# Microcontroller.net
KiCad netlist of a schematic drawn in Altium Designer
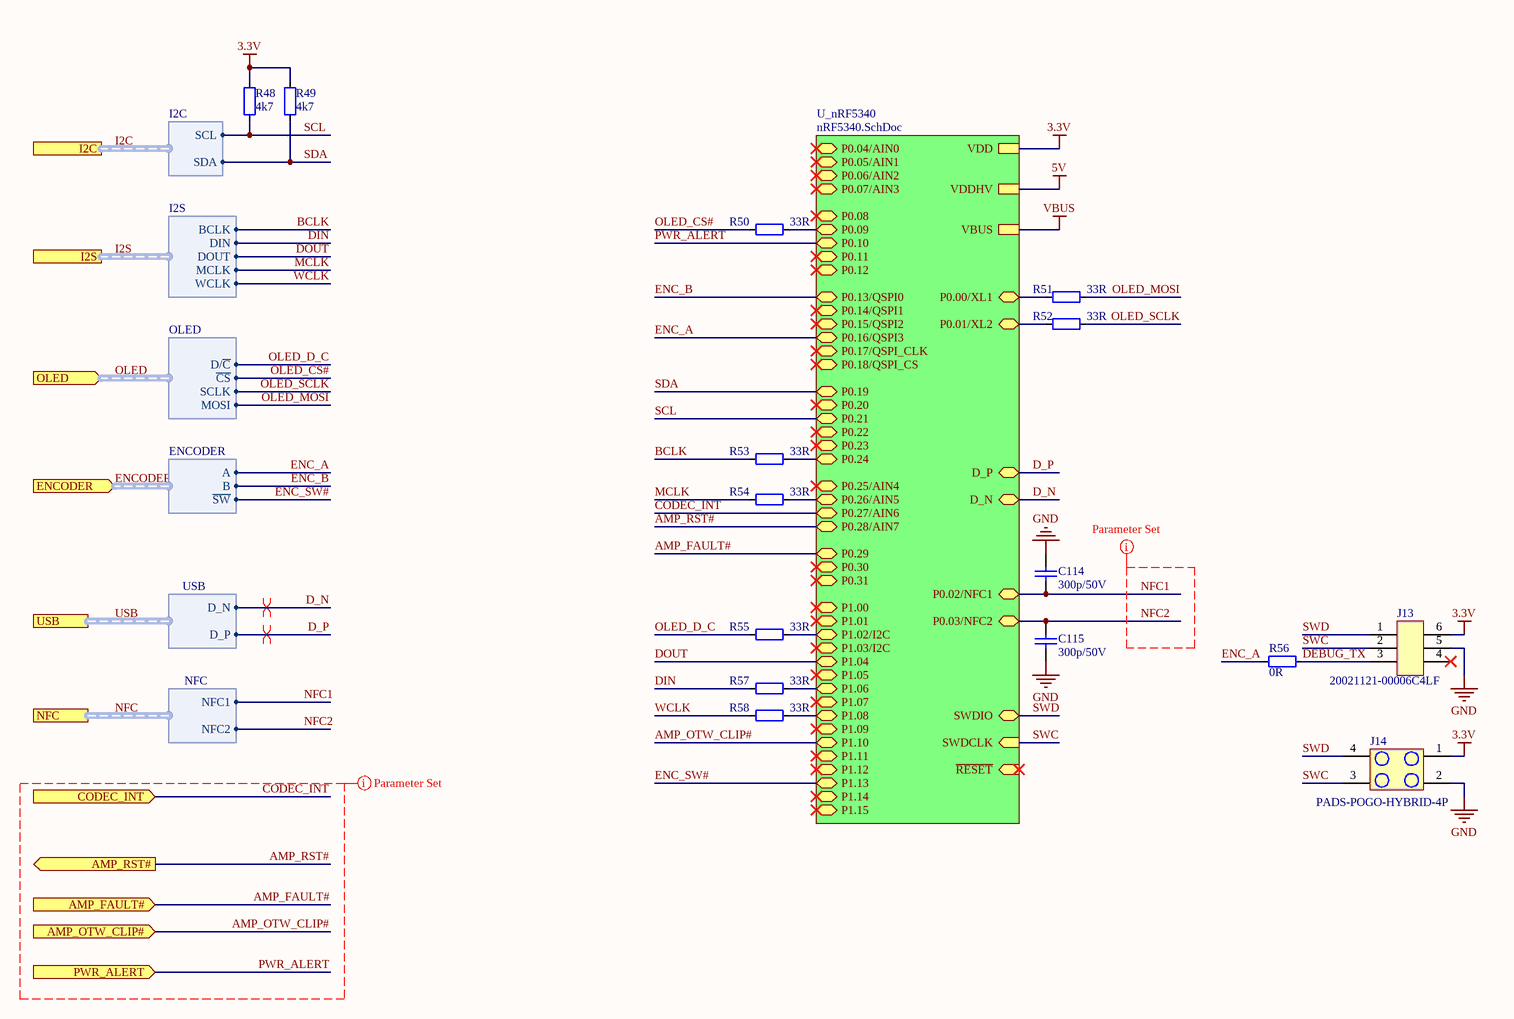
[diagram p0: Microcontroller.SchDoc]

(export (version "E")
  (design (tool "Eeschema 10.0.6"))
  (components
    (comp (ref "C114")
      (value "300p/50V")
      (footprint "C0402")
      (fields (field (name "VOLTAGE") "50V") (field (name "TOLERANCE") "10%"))
      (libsource (lib "dk_capacitors") (part "300p 50V X7R 0402"))
    )
    (comp (ref "C115")
      (value "300p/50V")
      (footprint "C0402")
      (fields (field (name "VOLTAGE") "50V") (field (name "TOLERANCE") "10%"))
      (libsource (lib "dk_capacitors") (part "300p 50V X7R 0402"))
    )
    (comp (ref "J13")
      (value "20021121-00006C4LF")
      (footprint "20021121-00006C4LF")
      (description "Connector Header Surface Mount 6 position 0.050\" (1.27mm)")
      (libsource (lib "dk_connectors") (part "20021121-00006C4LF"))
    )
    (comp (ref "J14")
      (value "PADS-POGO-HYBRID-4P")
      (footprint "PADS-POGO-HYBRID-4P")
      (description "Pads for 4 pin programming pogoor smd header")
      (libsource (lib "dk_connectors") (part "PADS-POGO-HYBRID-4P"))
    )
    (comp (ref "R48")
      (value "4k7")
      (footprint "R0402")
      (fields (field (name "TOLERANCE") "1%") (field (name "VOLTAGE") "50V"))
      (libsource (lib "dk_resistors") (part "4k7 63mW 50V 0402"))
    )
    (comp (ref "R49")
      (value "4k7")
      (footprint "R0402")
      (fields (field (name "TOLERANCE") "1%") (field (name "VOLTAGE") "50V"))
      (libsource (lib "dk_resistors") (part "4k7 63mW 50V 0402"))
    )
    (comp (ref "R50")
      (value "33R")
      (footprint "R0402")
      (fields (field (name "TOLERANCE") "5%") (field (name "VOLTAGE") "50V"))
      (libsource (lib "dk_resistors") (part "33R 63mW 50V 0402"))
    )
    (comp (ref "R51")
      (value "33R")
      (footprint "R0402")
      (fields (field (name "TOLERANCE") "5%") (field (name "VOLTAGE") "50V"))
      (libsource (lib "") (part "33R 63mW 50V 0402_1"))
    )
    (comp (ref "R52")
      (value "33R")
      (footprint "R0402")
      (fields (field (name "TOLERANCE") "5%") (field (name "VOLTAGE") "50V"))
      (libsource (lib "") (part "33R 63mW 50V 0402_1"))
    )
    (comp (ref "R53")
      (value "33R")
      (footprint "R0402")
      (fields (field (name "TOLERANCE") "5%") (field (name "VOLTAGE") "50V"))
      (libsource (lib "dk_resistors") (part "33R 63mW 50V 0402"))
    )
    (comp (ref "R54")
      (value "33R")
      (footprint "R0402")
      (fields (field (name "TOLERANCE") "5%") (field (name "VOLTAGE") "50V"))
      (libsource (lib "dk_resistors") (part "33R 63mW 50V 0402"))
    )
    (comp (ref "R55")
      (value "33R")
      (footprint "R0402")
      (fields (field (name "TOLERANCE") "5%") (field (name "VOLTAGE") "50V"))
      (libsource (lib "dk_resistors") (part "33R 63mW 50V 0402"))
    )
    (comp (ref "R56")
      (value "0R")
      (footprint "R0402")
      (fields (field (name "TOLERANCE") "1%") (field (name "VOLTAGE") "50V"))
      (libsource (lib "dk_resistors") (part "0R 63mW 50V 0402"))
    )
    (comp (ref "R57")
      (value "33R")
      (footprint "R0402")
      (fields (field (name "TOLERANCE") "5%") (field (name "VOLTAGE") "50V"))
      (libsource (lib "dk_resistors") (part "33R 63mW 50V 0402"))
    )
    (comp (ref "R58")
      (value "33R")
      (footprint "R0402")
      (fields (field (name "TOLERANCE") "5%") (field (name "VOLTAGE") "50V"))
      (libsource (lib "dk_resistors") (part "33R 63mW 50V 0402"))
    )
  )
  (nets
    (net (code "10") (name "/BCLK") (class "Default")
      (node (ref "R53") (pin "1") (pinfunction "1_1") (pintype "passive"))
    )
    (net (code "12") (name "/DEBUG_TX") (class "Default")
      (node (ref "J13") (pin "3") (pintype "passive"))
      (node (ref "R56") (pin "2") (pinfunction "2_2") (pintype "passive"))
    )
    (net (code "13") (name "/DIN") (class "Default")
      (node (ref "R57") (pin "1") (pinfunction "1_1") (pintype "passive"))
    )
    (net (code "18") (name "/ENC_A") (class "Default")
      (node (ref "R56") (pin "1") (pinfunction "1_1") (pintype "passive"))
    )
    (net (code "23") (name "/MCLK") (class "Default")
      (node (ref "R54") (pin "1") (pinfunction "1_1") (pintype "passive"))
    )
    (net (code "24") (name "/NFC1") (class "Default")
      (node (ref "C114") (pin "1") (pinfunction "1_1") (pintype "passive"))
    )
    (net (code "25") (name "/NFC2") (class "Default")
      (node (ref "C115") (pin "2") (pinfunction "2_2") (pintype "passive"))
    )
    (net (code "27") (name "/OLED_CS#") (class "Default")
      (node (ref "R50") (pin "1") (pinfunction "1_1") (pintype "passive"))
    )
    (net (code "28") (name "/OLED_D_C") (class "Default")
      (node (ref "R55") (pin "1") (pinfunction "1_1") (pintype "passive"))
    )
    (net (code "29") (name "/OLED_MOSI") (class "Default")
      (node (ref "R51") (pin "1") (pinfunction "1_1") (pintype "passive"))
    )
    (net (code "30") (name "/OLED_SCLK") (class "Default")
      (node (ref "R52") (pin "1") (pinfunction "1_1") (pintype "passive"))
    )
    (net (code "32") (name "/P0.00{slash}XL1") (class "Default")
      (node (ref "R51") (pin "2") (pinfunction "2_2") (pintype "passive"))
    )
    (net (code "33") (name "/P0.01{slash}XL2") (class "Default")
      (node (ref "R52") (pin "2") (pinfunction "2_2") (pintype "passive"))
    )
    (net (code "39") (name "/P0.09") (class "Default")
      (node (ref "R50") (pin "2") (pinfunction "2_2") (pintype "passive"))
    )
    (net (code "49") (name "/P0.24") (class "Default")
      (node (ref "R53") (pin "2") (pinfunction "2_2") (pintype "passive"))
    )
    (net (code "51") (name "/P0.26{slash}AIN5") (class "Default")
      (node (ref "R54") (pin "2") (pinfunction "2_2") (pintype "passive"))
    )
    (net (code "56") (name "/P1.02{slash}I2C") (class "Default")
      (node (ref "R55") (pin "2") (pinfunction "2_2") (pintype "passive"))
    )
    (net (code "59") (name "/P1.06") (class "Default")
      (node (ref "R57") (pin "2") (pinfunction "2_2") (pintype "passive"))
    )
    (net (code "61") (name "/P1.08") (class "Default")
      (node (ref "R58") (pin "2") (pinfunction "2_2") (pintype "passive"))
    )
    (net (code "68") (name "/SCL") (class "Default")
      (node (ref "R48") (pin "1") (pinfunction "1_1") (pintype "passive"))
    )
    (net (code "69") (name "/SDA") (class "Default")
      (node (ref "R49") (pin "1") (pinfunction "1_1") (pintype "passive"))
    )
    (net (code "70") (name "/SWC") (class "Default")
      (node (ref "J13") (pin "2") (pintype "passive"))
      (node (ref "J14") (pin "3") (pintype "passive"))
    )
    (net (code "71") (name "/SWD") (class "Default")
      (node (ref "J13") (pin "1") (pintype "passive"))
      (node (ref "J14") (pin "4") (pintype "passive"))
    )
    (net (code "73") (name "/WCLK") (class "Default")
      (node (ref "R58") (pin "1") (pinfunction "1_1") (pintype "passive"))
    )
    (net (code "75") (name "3.3V") (class "Default")
      (node (ref "J13") (pin "6") (pintype "passive"))
      (node (ref "J14") (pin "1") (pintype "passive"))
      (node (ref "R48") (pin "2") (pinfunction "2_2") (pintype "passive"))
      (node (ref "R49") (pin "2") (pinfunction "2_2") (pintype "passive"))
    )
    (net (code "77") (name "GND") (class "Default")
      (node (ref "C114") (pin "2") (pinfunction "2_2") (pintype "passive"))
      (node (ref "C115") (pin "1") (pinfunction "1_1") (pintype "passive"))
      (node (ref "J13") (pin "5") (pintype "passive"))
      (node (ref "J14") (pin "2") (pintype "passive"))
    )
    (net (code "79") (name "unconnected-(J13-Pad4)") (class "Default")
      (node (ref "J13") (pin "4") (pintype "passive+no_connect"))
    )
  )
)
